# I2Ciso_module_v10.net
KiCad netlist of a schematic drawn in EAGLE
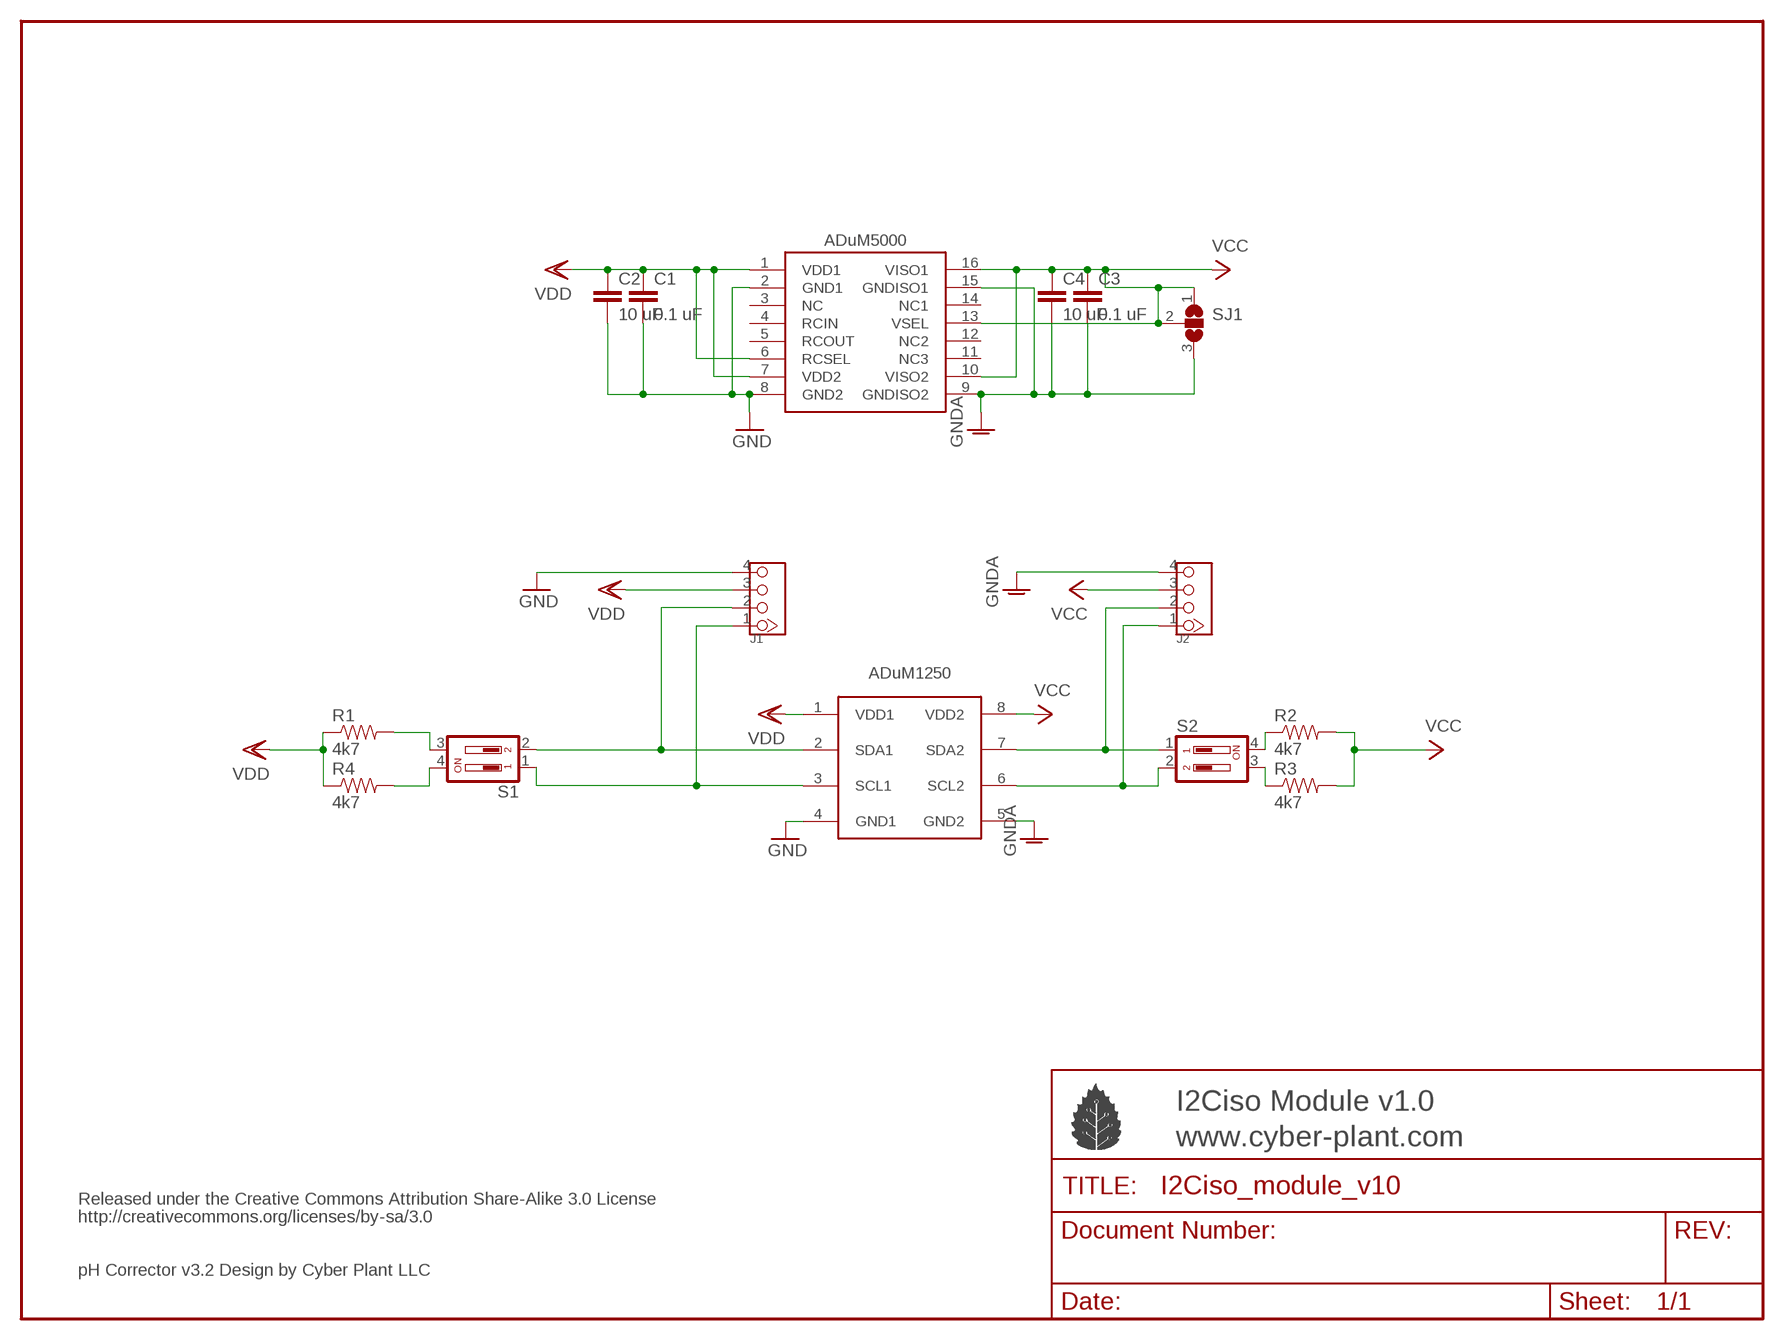
[diagram p0: schematic, sheet 1]

(export (version "E")
  (design (tool "Eeschema 10.0.6"))
  (components
    (comp (ref "C1")
      (value "0.1 uF")
      (footprint "eagle-import:1206")
      (libsource (lib "eagle-import") (part "CAP1206"))
    )
    (comp (ref "C2")
      (value "10 uF")
      (footprint "eagle-import:1206")
      (libsource (lib "eagle-import") (part "CAP1206"))
    )
    (comp (ref "C3")
      (value "0.1 uF")
      (footprint "eagle-import:1206")
      (libsource (lib "eagle-import") (part "CAP1206"))
    )
    (comp (ref "C4")
      (value "10 uF")
      (footprint "eagle-import:1206")
      (libsource (lib "eagle-import") (part "CAP1206"))
    )
    (comp (ref "J1")
      (value "TWIG-4P-2.090D")
      (footprint "eagle-import:4P-2.0-90D")
      (libsource (lib "eagle-import") (part "TWIG-4P-2.090D"))
    )
    (comp (ref "J2")
      (value "TWIG-4P-2.090D")
      (footprint "eagle-import:4P-2.0-90D")
      (libsource (lib "eagle-import") (part "TWIG-4P-2.090D"))
    )
    (comp (ref "R1")
      (value "4k7")
      (footprint "eagle-import:1206")
      (libsource (lib "eagle-import") (part "RESISTOR1206"))
    )
    (comp (ref "R2")
      (value "4k7")
      (footprint "eagle-import:1206")
      (libsource (lib "eagle-import") (part "RESISTOR1206"))
    )
    (comp (ref "R3")
      (value "4k7")
      (footprint "eagle-import:1206")
      (libsource (lib "eagle-import") (part "RESISTOR1206"))
    )
    (comp (ref "R4")
      (value "4k7")
      (footprint "eagle-import:1206")
      (libsource (lib "eagle-import") (part "RESISTOR1206"))
    )
    (comp (ref "S1")
      (value "DS02")
      (footprint "eagle-import:DS-02")
      (libsource (lib "eagle-import") (part "DS02"))
    )
    (comp (ref "S2")
      (value "DS02")
      (footprint "eagle-import:DS-02")
      (libsource (lib "eagle-import") (part "DS02"))
    )
    (comp (ref "SJ1")
      (value "SJ2W")
      (footprint "eagle-import:SJ_2")
      (libsource (lib "eagle-import") (part "SJ2W"))
    )
    (comp (ref "U$3")
      (value "ADUM1251")
      (footprint "eagle-import:SO8")
      (libsource (lib "eagle-import") (part "ADUM1251"))
    )
    (comp (ref "U$4")
      (value "ADUM5000")
      (footprint "eagle-import:SO-16W")
      (libsource (lib "eagle-import") (part "ADUM5000"))
    )
  )
  (nets
    (net (code "1") (name "GND") (class "Default")
      (node (ref "C1") (pin "2") (pinfunction "2_2") (pintype "passive"))
      (node (ref "C2") (pin "2") (pinfunction "2_2") (pintype "passive"))
      (node (ref "J1") (pin "4") (pinfunction "4_4") (pintype "bidirectional"))
      (node (ref "U$3") (pin "4") (pinfunction "GND1_4") (pintype "bidirectional"))
      (node (ref "U$4") (pin "2") (pinfunction "GND1_2") (pintype "bidirectional"))
      (node (ref "U$4") (pin "8") (pinfunction "GND2_8") (pintype "bidirectional"))
    )
    (net (code "2") (name "GNDA") (class "Default")
      (node (ref "C3") (pin "2") (pinfunction "2_2") (pintype "passive"))
      (node (ref "C4") (pin "2") (pinfunction "2_2") (pintype "passive"))
      (node (ref "J2") (pin "4") (pinfunction "4_4") (pintype "bidirectional"))
      (node (ref "SJ1") (pin "3") (pinfunction "3_3") (pintype "passive"))
      (node (ref "U$3") (pin "5") (pinfunction "GND2_5") (pintype "bidirectional"))
      (node (ref "U$4") (pin "15") (pinfunction "GNDISO1_15") (pintype "bidirectional"))
      (node (ref "U$4") (pin "9") (pinfunction "GNDISO2_9") (pintype "bidirectional"))
    )
    (net (code "3") (name "Net-(R1-Pad2)") (class "Default")
      (node (ref "R1") (pin "2") (pinfunction "2_2") (pintype "passive"))
      (node (ref "S1") (pin "3") (pinfunction "3_3") (pintype "passive"))
    )
    (net (code "4") (name "Net-(R2-Pad1)") (class "Default")
      (node (ref "R2") (pin "1") (pinfunction "1_1") (pintype "passive"))
      (node (ref "S2") (pin "4") (pinfunction "4_4") (pintype "passive"))
    )
    (net (code "5") (name "Net-(R3-Pad1)") (class "Default")
      (node (ref "R3") (pin "1") (pinfunction "1_1") (pintype "passive"))
      (node (ref "S2") (pin "3") (pinfunction "3_3") (pintype "passive"))
    )
    (net (code "6") (name "Net-(R4-Pad2)") (class "Default")
      (node (ref "R4") (pin "2") (pinfunction "2_2") (pintype "passive"))
      (node (ref "S1") (pin "4") (pinfunction "4_4") (pintype "passive"))
    )
    (net (code "7") (name "Net-(U$3-SCL1)") (class "Default")
      (node (ref "J1") (pin "1") (pinfunction "1_1") (pintype "bidirectional"))
      (node (ref "S1") (pin "1") (pinfunction "1_1") (pintype "passive"))
      (node (ref "U$3") (pin "3") (pinfunction "SCL1_3") (pintype "bidirectional"))
    )
    (net (code "8") (name "Net-(U$3-SCL2)") (class "Default")
      (node (ref "J2") (pin "1") (pinfunction "1_1") (pintype "bidirectional"))
      (node (ref "S2") (pin "2") (pinfunction "2_2") (pintype "passive"))
      (node (ref "U$3") (pin "6") (pinfunction "SCL2_6") (pintype "bidirectional"))
    )
    (net (code "9") (name "Net-(U$3-SDA1)") (class "Default")
      (node (ref "J1") (pin "2") (pinfunction "2_2") (pintype "bidirectional"))
      (node (ref "S1") (pin "2") (pinfunction "2_2") (pintype "passive"))
      (node (ref "U$3") (pin "2") (pinfunction "SDA1_2") (pintype "bidirectional"))
    )
    (net (code "10") (name "Net-(U$3-SDA2)") (class "Default")
      (node (ref "J2") (pin "2") (pinfunction "2_2") (pintype "bidirectional"))
      (node (ref "S2") (pin "1") (pinfunction "1_1") (pintype "passive"))
      (node (ref "U$3") (pin "7") (pinfunction "SDA2_7") (pintype "bidirectional"))
    )
    (net (code "11") (name "VCC") (class "Default")
      (node (ref "C3") (pin "1") (pinfunction "1_1") (pintype "passive"))
      (node (ref "C4") (pin "1") (pinfunction "1_1") (pintype "passive"))
      (node (ref "J2") (pin "3") (pinfunction "3_3") (pintype "bidirectional"))
      (node (ref "R2") (pin "2") (pinfunction "2_2") (pintype "passive"))
      (node (ref "R3") (pin "2") (pinfunction "2_2") (pintype "passive"))
      (node (ref "SJ1") (pin "1") (pinfunction "1_1") (pintype "passive"))
      (node (ref "SJ1") (pin "2") (pinfunction "2_2") (pintype "passive"))
      (node (ref "U$3") (pin "8") (pinfunction "VDD2_8") (pintype "bidirectional"))
      (node (ref "U$4") (pin "10") (pinfunction "VISO2_10") (pintype "bidirectional"))
      (node (ref "U$4") (pin "13") (pinfunction "VSEL_13") (pintype "output"))
      (node (ref "U$4") (pin "16") (pinfunction "VISO1_16") (pintype "bidirectional"))
    )
    (net (code "12") (name "VDD") (class "Default")
      (node (ref "C1") (pin "1") (pinfunction "1_1") (pintype "passive"))
      (node (ref "C2") (pin "1") (pinfunction "1_1") (pintype "passive"))
      (node (ref "J1") (pin "3") (pinfunction "3_3") (pintype "bidirectional"))
      (node (ref "R1") (pin "1") (pinfunction "1_1") (pintype "passive"))
      (node (ref "R4") (pin "1") (pinfunction "1_1") (pintype "passive"))
      (node (ref "U$3") (pin "1") (pinfunction "VDD1_1") (pintype "bidirectional"))
      (node (ref "U$4") (pin "1") (pinfunction "VDD1_1") (pintype "bidirectional"))
      (node (ref "U$4") (pin "6") (pinfunction "RCSEL_6") (pintype "input"))
      (node (ref "U$4") (pin "7") (pinfunction "VDD2_7") (pintype "bidirectional"))
    )
    (net (code "13") (name "unconnected-(U$4-NC-Pad3)") (class "Default")
      (node (ref "U$4") (pin "3") (pinfunction "NC_3") (pintype "no_connect"))
    )
    (net (code "14") (name "unconnected-(U$4-NC1-Pad14)") (class "Default")
      (node (ref "U$4") (pin "14") (pinfunction "NC1_14") (pintype "no_connect"))
    )
    (net (code "15") (name "unconnected-(U$4-NC2-Pad12)") (class "Default")
      (node (ref "U$4") (pin "12") (pinfunction "NC2_12") (pintype "no_connect"))
    )
    (net (code "16") (name "unconnected-(U$4-NC3-Pad11)") (class "Default")
      (node (ref "U$4") (pin "11") (pinfunction "NC3_11") (pintype "no_connect"))
    )
    (net (code "17") (name "unconnected-(U$4-RCIN-Pad4)") (class "Default")
      (node (ref "U$4") (pin "4") (pinfunction "RCIN_4") (pintype "input"))
    )
    (net (code "18") (name "unconnected-(U$4-RCOUT-Pad5)") (class "Default")
      (node (ref "U$4") (pin "5") (pinfunction "RCOUT_5") (pintype "output"))
    )
  )
)
